# NexitonAdapterBoard.net
KiCad netlist of a schematic drawn in Altium Designer
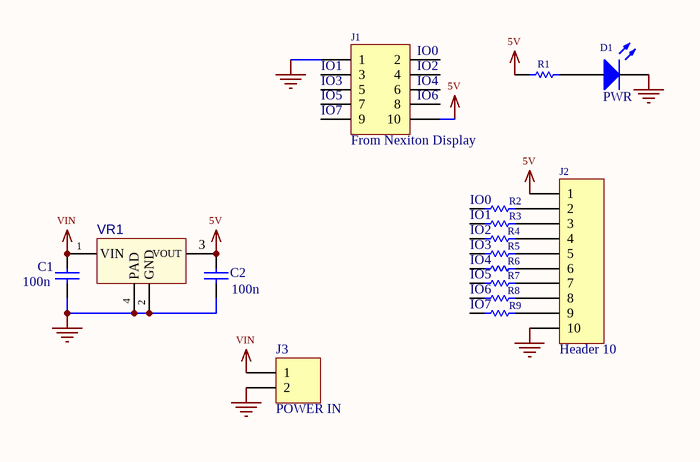
[diagram p0: NexitonAdapterBoard.SchDoc]

(export (version "E")
  (design (tool "Eeschema 10.0.6"))
  (components
    (comp (ref "C1")
      (value "100n")
      (footprint "RES_0805")
      (description "Capacitor (Semiconductor SIM Model)")
      (fields (field (name "Comment") "Cap Semi") (field (name "PUBLISHER") "Altium Limited"))
      (libsource (lib "Miscellaneous Devices") (part "Cap Semi"))
    )
    (comp (ref "C2")
      (value "100n")
      (footprint "RES_0805")
      (description "Capacitor (Semiconductor SIM Model)")
      (fields (field (name "Comment") "Cap Semi") (field (name "PUBLISHER") "Altium Limited"))
      (libsource (lib "Miscellaneous Devices") (part "Cap Semi"))
    )
    (comp (ref "D1")
      (value "PWR")
      (footprint "LED-0805")
      (fields (field (name "PUBLISHER") "Altium Limited"))
      (libsource (lib "Miscellaneous Devices") (part "LED0"))
    )
    (comp (ref "J1")
      (value "From Nexiton Display")
      (footprint "HDR2X5")
      (description "Header, 5-Pin, Dual row")
      (fields (field (name "PUBLISHER") "Altium Limited"))
      (libsource (lib "Miscellaneous Connectors") (part "Header 5X2"))
    )
    (comp (ref "J2")
      (value "Header 10")
      (footprint "HDR1X10")
      (description "Header, 10-Pin")
      (fields (field (name "PUBLISHER") "Altium Limited"))
      (libsource (lib "Miscellaneous Connectors") (part "Header 10"))
    )
    (comp (ref "J3")
      (value "POWER IN")
      (footprint "HDR1X2")
      (description "Header, 2-Pin")
      (fields (field (name "PUBLISHER") "Altium Limited"))
      (libsource (lib "Miscellaneous Connectors") (part "Header 2"))
    )
    (comp (ref "R1")
      (value "Res1")
      (footprint "RESC0805(2012)_M")
      (description "Resistor")
      (fields (field (name "PUBLISHER") "Altium Limited"))
      (libsource (lib "Miscellaneous Devices") (part "Res1"))
    )
    (comp (ref "R2")
      (value "Res1")
      (footprint "RESC0805(2012)_M")
      (description "Resistor")
      (fields (field (name "PUBLISHER") "Altium Limited"))
      (libsource (lib "Miscellaneous Devices") (part "Res1"))
    )
    (comp (ref "R3")
      (value "Res1")
      (footprint "RESC0805(2012)_M")
      (description "Resistor")
      (fields (field (name "PUBLISHER") "Altium Limited"))
      (libsource (lib "Miscellaneous Devices") (part "Res1"))
    )
    (comp (ref "R4")
      (value "Res1")
      (footprint "RESC0805(2012)_M")
      (description "Resistor")
      (fields (field (name "PUBLISHER") "Altium Limited"))
      (libsource (lib "Miscellaneous Devices") (part "Res1"))
    )
    (comp (ref "R5")
      (value "Res1")
      (footprint "RESC0805(2012)_M")
      (description "Resistor")
      (fields (field (name "PUBLISHER") "Altium Limited"))
      (libsource (lib "Miscellaneous Devices") (part "Res1"))
    )
    (comp (ref "R6")
      (value "Res1")
      (footprint "RESC0805(2012)_M")
      (description "Resistor")
      (fields (field (name "PUBLISHER") "Altium Limited"))
      (libsource (lib "Miscellaneous Devices") (part "Res1"))
    )
    (comp (ref "R7")
      (value "Res1")
      (footprint "RESC0805(2012)_M")
      (description "Resistor")
      (fields (field (name "PUBLISHER") "Altium Limited"))
      (libsource (lib "Miscellaneous Devices") (part "Res1"))
    )
    (comp (ref "R8")
      (value "Res1")
      (footprint "RESC0805(2012)_M")
      (description "Resistor")
      (fields (field (name "PUBLISHER") "Altium Limited"))
      (libsource (lib "Miscellaneous Devices") (part "Res1"))
    )
    (comp (ref "R9")
      (value "Res1")
      (footprint "RESC0805(2012)_M")
      (description "Resistor")
      (fields (field (name "PUBLISHER") "Altium Limited"))
      (libsource (lib "Miscellaneous Devices") (part "Res1"))
    )
    (comp (ref "VR1")
      (value "LDL1117S50R")
      (footprint "SOT223_M")
      (description "Fixed 5V Voltage Regulator")
      (fields (field (name "MFR") "TI") (field (name "MPN") "LM340MP-5.0"))
      (libsource (lib "105848_revD3") (part "LM317"))
    )
  )
  (nets
    (net (code "1") (name "/IO0") (class "Default")
      (node (ref "J1") (pin "2") (pinfunction "2_2") (pintype "passive"))
      (node (ref "R2") (pin "1") (pinfunction "1_1") (pintype "passive"))
    )
    (net (code "2") (name "/IO1") (class "Default")
      (node (ref "J1") (pin "3") (pinfunction "3_3") (pintype "passive"))
      (node (ref "R3") (pin "1") (pinfunction "1_1") (pintype "passive"))
    )
    (net (code "3") (name "/IO2") (class "Default")
      (node (ref "J1") (pin "4") (pinfunction "4_4") (pintype "passive"))
      (node (ref "R4") (pin "1") (pinfunction "1_1") (pintype "passive"))
    )
    (net (code "4") (name "/IO3") (class "Default")
      (node (ref "J1") (pin "5") (pinfunction "5_5") (pintype "passive"))
      (node (ref "R5") (pin "1") (pinfunction "1_1") (pintype "passive"))
    )
    (net (code "5") (name "/IO4") (class "Default")
      (node (ref "J1") (pin "6") (pinfunction "6_6") (pintype "passive"))
      (node (ref "R6") (pin "1") (pinfunction "1_1") (pintype "passive"))
    )
    (net (code "6") (name "/IO5") (class "Default")
      (node (ref "J1") (pin "7") (pinfunction "7_7") (pintype "passive"))
      (node (ref "R7") (pin "1") (pinfunction "1_1") (pintype "passive"))
    )
    (net (code "7") (name "/IO6") (class "Default")
      (node (ref "J1") (pin "8") (pinfunction "8_8") (pintype "passive"))
      (node (ref "R8") (pin "1") (pinfunction "1_1") (pintype "passive"))
    )
    (net (code "8") (name "/IO7") (class "Default")
      (node (ref "J1") (pin "9") (pinfunction "9_9") (pintype "passive"))
      (node (ref "R9") (pin "1") (pinfunction "1_1") (pintype "passive"))
    )
    (net (code "9") (name "5V") (class "Default")
      (node (ref "C2") (pin "2") (pinfunction "2_2") (pintype "passive"))
      (node (ref "J1") (pin "10") (pinfunction "10_10") (pintype "passive"))
      (node (ref "J2") (pin "1") (pinfunction "1_1") (pintype "passive"))
      (node (ref "R1") (pin "1") (pinfunction "1_1") (pintype "passive"))
      (node (ref "VR1") (pin "3") (pinfunction "VOUT_3") (pintype "passive"))
    )
    (net (code "10") (name "GND") (class "Default")
      (node (ref "C1") (pin "1") (pinfunction "1_1") (pintype "passive"))
      (node (ref "C2") (pin "1") (pinfunction "1_1") (pintype "passive"))
      (node (ref "D1") (pin "2") (pinfunction "+_2") (pintype "passive"))
      (node (ref "J1") (pin "1") (pinfunction "1_1") (pintype "passive"))
      (node (ref "J2") (pin "10") (pinfunction "10_10") (pintype "passive"))
      (node (ref "J3") (pin "2") (pinfunction "2_2") (pintype "passive"))
      (node (ref "VR1") (pin "2") (pinfunction "GND_2") (pintype "passive"))
      (node (ref "VR1") (pin "4") (pinfunction "PAD_4") (pintype "passive"))
    )
    (net (code "11") (name "Net-(D1--)") (class "Default")
      (node (ref "D1") (pin "1") (pinfunction "-_1") (pintype "passive"))
      (node (ref "R1") (pin "2") (pinfunction "2_2") (pintype "passive"))
    )
    (net (code "12") (name "Net-(J2-Pad2)") (class "Default")
      (node (ref "J2") (pin "2") (pinfunction "2_2") (pintype "passive"))
      (node (ref "R2") (pin "2") (pinfunction "2_2") (pintype "passive"))
    )
    (net (code "13") (name "Net-(J2-Pad3)") (class "Default")
      (node (ref "J2") (pin "3") (pinfunction "3_3") (pintype "passive"))
      (node (ref "R3") (pin "2") (pinfunction "2_2") (pintype "passive"))
    )
    (net (code "14") (name "Net-(J2-Pad4)") (class "Default")
      (node (ref "J2") (pin "4") (pinfunction "4_4") (pintype "passive"))
      (node (ref "R4") (pin "2") (pinfunction "2_2") (pintype "passive"))
    )
    (net (code "15") (name "Net-(J2-Pad5)") (class "Default")
      (node (ref "J2") (pin "5") (pinfunction "5_5") (pintype "passive"))
      (node (ref "R5") (pin "2") (pinfunction "2_2") (pintype "passive"))
    )
    (net (code "16") (name "Net-(J2-Pad6)") (class "Default")
      (node (ref "J2") (pin "6") (pinfunction "6_6") (pintype "passive"))
      (node (ref "R6") (pin "2") (pinfunction "2_2") (pintype "passive"))
    )
    (net (code "17") (name "Net-(J2-Pad7)") (class "Default")
      (node (ref "J2") (pin "7") (pinfunction "7_7") (pintype "passive"))
      (node (ref "R7") (pin "2") (pinfunction "2_2") (pintype "passive"))
    )
    (net (code "18") (name "Net-(J2-Pad8)") (class "Default")
      (node (ref "J2") (pin "8") (pinfunction "8_8") (pintype "passive"))
      (node (ref "R8") (pin "2") (pinfunction "2_2") (pintype "passive"))
    )
    (net (code "19") (name "Net-(J2-Pad9)") (class "Default")
      (node (ref "J2") (pin "9") (pinfunction "9_9") (pintype "passive"))
      (node (ref "R9") (pin "2") (pinfunction "2_2") (pintype "passive"))
    )
    (net (code "20") (name "VIN") (class "Default")
      (node (ref "C1") (pin "2") (pinfunction "2_2") (pintype "passive"))
      (node (ref "J3") (pin "1") (pinfunction "1_1") (pintype "passive"))
      (node (ref "VR1") (pin "1") (pinfunction "VIN_1") (pintype "passive"))
    )
  )
)
